# Ornament.net
KiCad netlist of a schematic drawn in Altium Designer
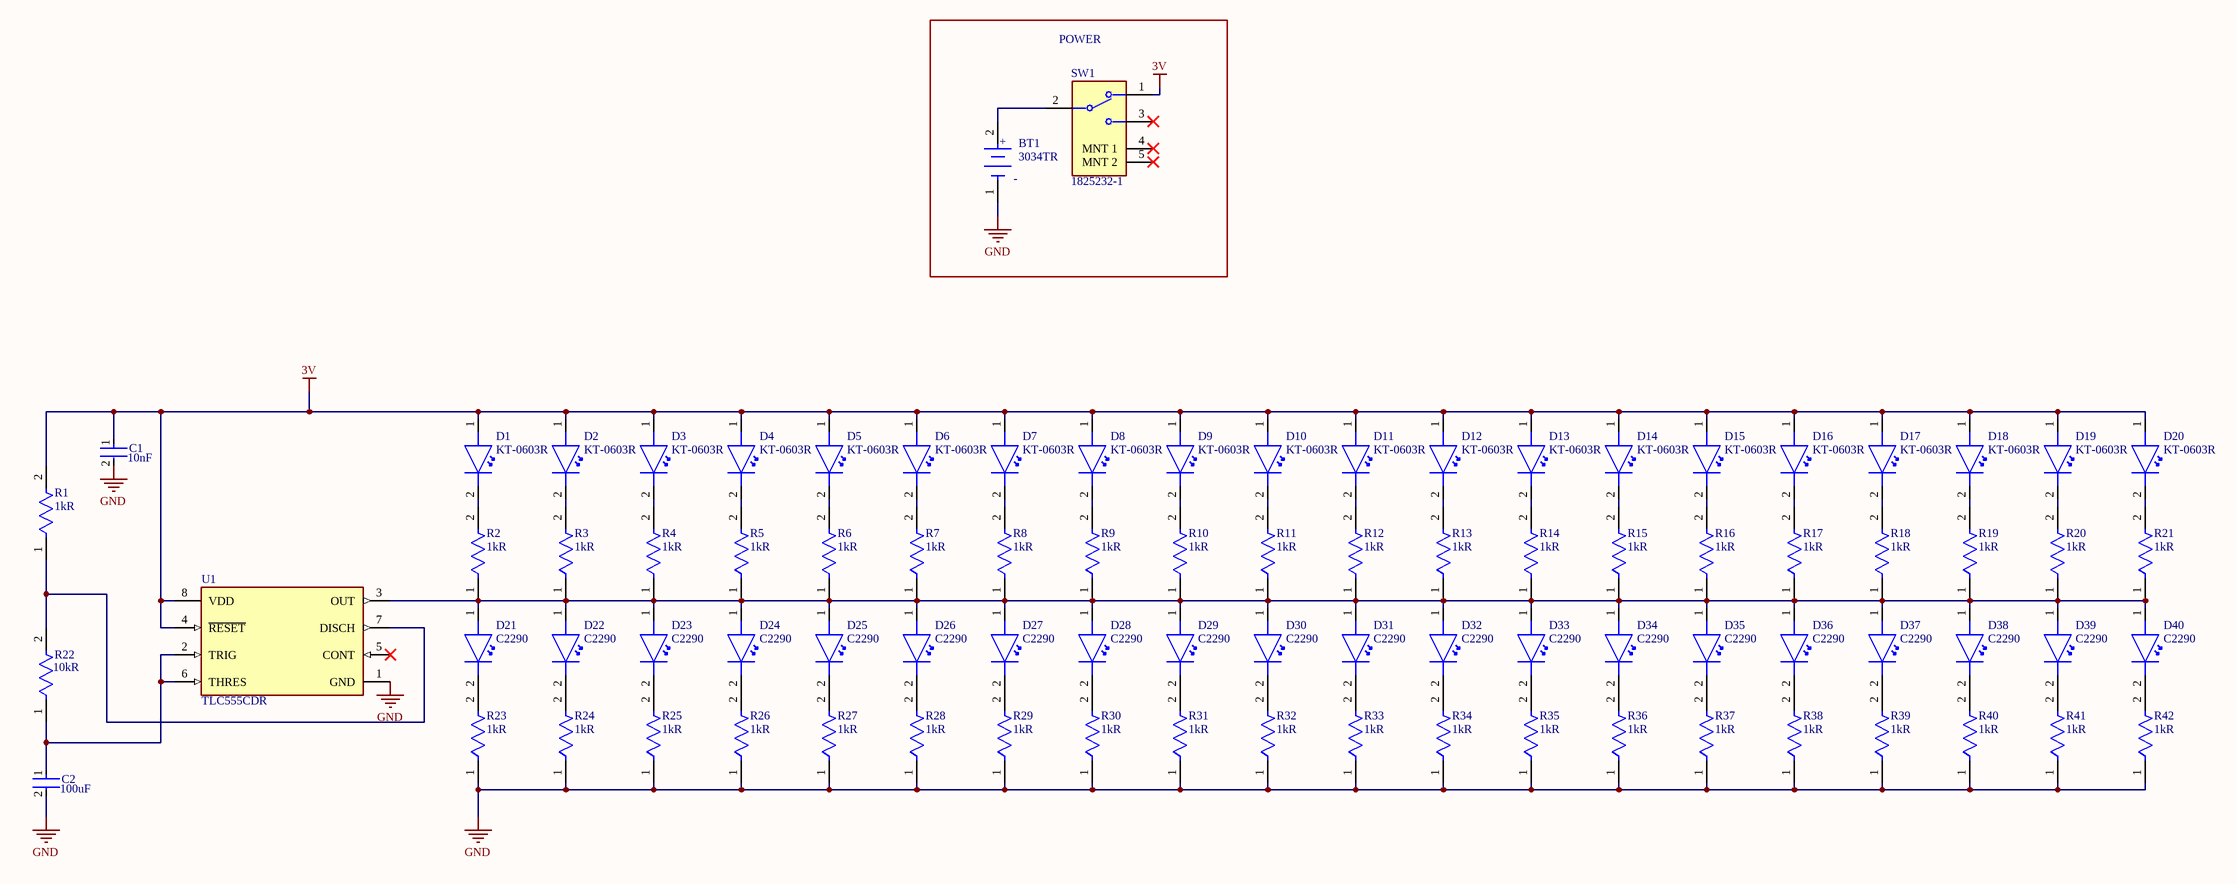
[diagram p0: Ornament.SchDoc]

(export (version "E")
  (design (tool "Eeschema 10.0.6"))
  (components
    (comp (ref "BT1")
      (value "3034TR")
      (footprint "FP-3034TR-MFG")
      (description "BATTERY RETAINER COIN 20MM SMD")
      (libsource (lib "Altium Content Vault") (part "a5284bd3cf3b31494a5f032c79b9da8"))
    )
    (comp (ref "C1")
      (value "CL05B103KB5NNNC")
      (footprint "FP-CL165-IPC_C")
      (description "Cap Ceramic 10nF 50V X7R ±10% SMD 0402 +125°C Paper T/R")
      (fields
        (field (name "VOLTAGE") "50V")
        (field (name "TOLERANCE") "10%")
        (field (name "CAPACITANCE") "10nF")
      )
      (libsource (lib "Altium Content Vault") (part "b4654b650e69147ec39a6b967a45e02"))
    )
    (comp (ref "C2")
      (value "JMK316BJ107ML-T")
      (footprint "FP-MK316L-MFG")
      (description "CAP CER 100UF 6.3V X5R 1206")
      (fields (field (name "CAPACITANCE") "100uF") (field (name "TOLERANCE") "2%"))
      (libsource (lib "Altium Content Vault") (part "b4654b650e69147ec39a6b967a45e02"))
    )
    (comp (ref "D1")
      (value "KT-0603R")
      (footprint "LED_0603")
      (description "Red 615~630nm 1.9~2.2V 0603 Light Emitting Diodes (LED) RoHS")
      (libsource (lib "Symbols") (part "KT-0603R"))
    )
    (comp (ref "D2")
      (value "KT-0603R")
      (footprint "LED_0603")
      (description "Red 615~630nm 1.9~2.2V 0603 Light Emitting Diodes (LED) RoHS")
      (libsource (lib "Symbols") (part "KT-0603R"))
    )
    (comp (ref "D3")
      (value "KT-0603R")
      (footprint "LED_0603")
      (description "Red 615~630nm 1.9~2.2V 0603 Light Emitting Diodes (LED) RoHS")
      (libsource (lib "Symbols") (part "KT-0603R"))
    )
    (comp (ref "D4")
      (value "KT-0603R")
      (footprint "LED_0603")
      (description "Red 615~630nm 1.9~2.2V 0603 Light Emitting Diodes (LED) RoHS")
      (libsource (lib "Symbols") (part "KT-0603R"))
    )
    (comp (ref "D5")
      (value "KT-0603R")
      (footprint "LED_0603")
      (description "Red 615~630nm 1.9~2.2V 0603 Light Emitting Diodes (LED) RoHS")
      (libsource (lib "Symbols") (part "KT-0603R"))
    )
    (comp (ref "D6")
      (value "KT-0603R")
      (footprint "LED_0603")
      (description "Red 615~630nm 1.9~2.2V 0603 Light Emitting Diodes (LED) RoHS")
      (libsource (lib "Symbols") (part "KT-0603R"))
    )
    (comp (ref "D7")
      (value "KT-0603R")
      (footprint "LED_0603")
      (description "Red 615~630nm 1.9~2.2V 0603 Light Emitting Diodes (LED) RoHS")
      (libsource (lib "Symbols") (part "KT-0603R"))
    )
    (comp (ref "D8")
      (value "KT-0603R")
      (footprint "LED_0603")
      (description "Red 615~630nm 1.9~2.2V 0603 Light Emitting Diodes (LED) RoHS")
      (libsource (lib "Symbols") (part "KT-0603R"))
    )
    (comp (ref "D9")
      (value "KT-0603R")
      (footprint "LED_0603")
      (description "Red 615~630nm 1.9~2.2V 0603 Light Emitting Diodes (LED) RoHS")
      (libsource (lib "Symbols") (part "KT-0603R"))
    )
    (comp (ref "D10")
      (value "KT-0603R")
      (footprint "LED_0603")
      (description "Red 615~630nm 1.9~2.2V 0603 Light Emitting Diodes (LED) RoHS")
      (libsource (lib "Symbols") (part "KT-0603R"))
    )
    (comp (ref "D11")
      (value "KT-0603R")
      (footprint "LED_0603")
      (description "Red 615~630nm 1.9~2.2V 0603 Light Emitting Diodes (LED) RoHS")
      (libsource (lib "Symbols") (part "KT-0603R"))
    )
    (comp (ref "D12")
      (value "KT-0603R")
      (footprint "LED_0603")
      (description "Red 615~630nm 1.9~2.2V 0603 Light Emitting Diodes (LED) RoHS")
      (libsource (lib "Symbols") (part "KT-0603R"))
    )
    (comp (ref "D13")
      (value "KT-0603R")
      (footprint "LED_0603")
      (description "Red 615~630nm 1.9~2.2V 0603 Light Emitting Diodes (LED) RoHS")
      (libsource (lib "Symbols") (part "KT-0603R"))
    )
    (comp (ref "D14")
      (value "KT-0603R")
      (footprint "LED_0603")
      (description "Red 615~630nm 1.9~2.2V 0603 Light Emitting Diodes (LED) RoHS")
      (libsource (lib "Symbols") (part "KT-0603R"))
    )
    (comp (ref "D15")
      (value "KT-0603R")
      (footprint "LED_0603")
      (description "Red 615~630nm 1.9~2.2V 0603 Light Emitting Diodes (LED) RoHS")
      (libsource (lib "Symbols") (part "KT-0603R"))
    )
    (comp (ref "D16")
      (value "KT-0603R")
      (footprint "LED_0603")
      (description "Red 615~630nm 1.9~2.2V 0603 Light Emitting Diodes (LED) RoHS")
      (libsource (lib "Symbols") (part "KT-0603R"))
    )
    (comp (ref "D17")
      (value "KT-0603R")
      (footprint "LED_0603")
      (description "Red 615~630nm 1.9~2.2V 0603 Light Emitting Diodes (LED) RoHS")
      (libsource (lib "Symbols") (part "KT-0603R"))
    )
    (comp (ref "D18")
      (value "KT-0603R")
      (footprint "LED_0603")
      (description "Red 615~630nm 1.9~2.2V 0603 Light Emitting Diodes (LED) RoHS")
      (libsource (lib "Symbols") (part "KT-0603R"))
    )
    (comp (ref "D19")
      (value "KT-0603R")
      (footprint "LED_0603")
      (description "Red 615~630nm 1.9~2.2V 0603 Light Emitting Diodes (LED) RoHS")
      (libsource (lib "Symbols") (part "KT-0603R"))
    )
    (comp (ref "D20")
      (value "KT-0603R")
      (footprint "LED_0603")
      (description "Red 615~630nm 1.9~2.2V 0603 Light Emitting Diodes (LED) RoHS")
      (libsource (lib "Symbols") (part "KT-0603R"))
    )
    (comp (ref "D21")
      (value "C2290")
      (footprint "LED_0603")
      (description "White 0603 Light Emitting Diodes (LED) RoHS")
      (libsource (lib "Symbols") (part "C2290"))
    )
    (comp (ref "D22")
      (value "C2290")
      (footprint "LED_0603")
      (description "White 0603 Light Emitting Diodes (LED) RoHS")
      (libsource (lib "Symbols") (part "C2290"))
    )
    (comp (ref "D23")
      (value "C2290")
      (footprint "LED_0603")
      (description "White 0603 Light Emitting Diodes (LED) RoHS")
      (libsource (lib "Symbols") (part "C2290"))
    )
    (comp (ref "D24")
      (value "C2290")
      (footprint "LED_0603")
      (description "White 0603 Light Emitting Diodes (LED) RoHS")
      (libsource (lib "Symbols") (part "C2290"))
    )
    (comp (ref "D25")
      (value "C2290")
      (footprint "LED_0603")
      (description "White 0603 Light Emitting Diodes (LED) RoHS")
      (libsource (lib "Symbols") (part "C2290"))
    )
    (comp (ref "D26")
      (value "C2290")
      (footprint "LED_0603")
      (description "White 0603 Light Emitting Diodes (LED) RoHS")
      (libsource (lib "Symbols") (part "C2290"))
    )
    (comp (ref "D27")
      (value "C2290")
      (footprint "LED_0603")
      (description "White 0603 Light Emitting Diodes (LED) RoHS")
      (libsource (lib "Symbols") (part "C2290"))
    )
    (comp (ref "D28")
      (value "C2290")
      (footprint "LED_0603")
      (description "White 0603 Light Emitting Diodes (LED) RoHS")
      (libsource (lib "Symbols") (part "C2290"))
    )
    (comp (ref "D29")
      (value "C2290")
      (footprint "LED_0603")
      (description "White 0603 Light Emitting Diodes (LED) RoHS")
      (libsource (lib "Symbols") (part "C2290"))
    )
    (comp (ref "D30")
      (value "C2290")
      (footprint "LED_0603")
      (description "White 0603 Light Emitting Diodes (LED) RoHS")
      (libsource (lib "Symbols") (part "C2290"))
    )
    (comp (ref "D31")
      (value "C2290")
      (footprint "LED_0603")
      (description "White 0603 Light Emitting Diodes (LED) RoHS")
      (libsource (lib "Symbols") (part "C2290"))
    )
    (comp (ref "D32")
      (value "C2290")
      (footprint "LED_0603")
      (description "White 0603 Light Emitting Diodes (LED) RoHS")
      (libsource (lib "Symbols") (part "C2290"))
    )
    (comp (ref "D33")
      (value "C2290")
      (footprint "LED_0603")
      (description "White 0603 Light Emitting Diodes (LED) RoHS")
      (libsource (lib "Symbols") (part "C2290"))
    )
    (comp (ref "D34")
      (value "C2290")
      (footprint "LED_0603")
      (description "White 0603 Light Emitting Diodes (LED) RoHS")
      (libsource (lib "Symbols") (part "C2290"))
    )
    (comp (ref "D35")
      (value "C2290")
      (footprint "LED_0603")
      (description "White 0603 Light Emitting Diodes (LED) RoHS")
      (libsource (lib "Symbols") (part "C2290"))
    )
    (comp (ref "D36")
      (value "C2290")
      (footprint "LED_0603")
      (description "White 0603 Light Emitting Diodes (LED) RoHS")
      (libsource (lib "Symbols") (part "C2290"))
    )
    (comp (ref "D37")
      (value "C2290")
      (footprint "LED_0603")
      (description "White 0603 Light Emitting Diodes (LED) RoHS")
      (libsource (lib "Symbols") (part "C2290"))
    )
    (comp (ref "D38")
      (value "C2290")
      (footprint "LED_0603")
      (description "White 0603 Light Emitting Diodes (LED) RoHS")
      (libsource (lib "Symbols") (part "C2290"))
    )
    (comp (ref "D39")
      (value "C2290")
      (footprint "LED_0603")
      (description "White 0603 Light Emitting Diodes (LED) RoHS")
      (libsource (lib "Symbols") (part "C2290"))
    )
    (comp (ref "D40")
      (value "C2290")
      (footprint "LED_0603")
      (description "White 0603 Light Emitting Diodes (LED) RoHS")
      (libsource (lib "Symbols") (part "C2290"))
    )
    (comp (ref "R1")
      (value "AC0402FR-071KL")
      (footprint "FP-AC0402-IPC_C")
      (description "RES 1kΩ ±1% 0.063W 0402")
      (fields (field (name "TOLERANCE") "1%") (field (name "RESISTANCE") "1kR"))
      (libsource (lib "Altium Content Vault") (part "1029c3af85768c4190bb7ad29bc67b5"))
    )
    (comp (ref "R2")
      (value "AC0402FR-071KL")
      (footprint "FP-AC0402-IPC_C")
      (description "RES 1kΩ ±1% 0.063W 0402")
      (fields (field (name "TOLERANCE") "1%") (field (name "RESISTANCE") "1kR"))
      (libsource (lib "Altium Content Vault") (part "1029c3af85768c4190bb7ad29bc67b5"))
    )
    (comp (ref "R3")
      (value "AC0402FR-071KL")
      (footprint "FP-AC0402-IPC_C")
      (description "RES 1kΩ ±1% 0.063W 0402")
      (fields (field (name "TOLERANCE") "1%") (field (name "RESISTANCE") "1kR"))
      (libsource (lib "Altium Content Vault") (part "1029c3af85768c4190bb7ad29bc67b5"))
    )
    (comp (ref "R4")
      (value "AC0402FR-071KL")
      (footprint "FP-AC0402-IPC_C")
      (description "RES 1kΩ ±1% 0.063W 0402")
      (fields (field (name "TOLERANCE") "1%") (field (name "RESISTANCE") "1kR"))
      (libsource (lib "Altium Content Vault") (part "1029c3af85768c4190bb7ad29bc67b5"))
    )
    (comp (ref "R5")
      (value "AC0402FR-071KL")
      (footprint "FP-AC0402-IPC_C")
      (description "RES 1kΩ ±1% 0.063W 0402")
      (fields (field (name "TOLERANCE") "1%") (field (name "RESISTANCE") "1kR"))
      (libsource (lib "Altium Content Vault") (part "1029c3af85768c4190bb7ad29bc67b5"))
    )
    (comp (ref "R6")
      (value "AC0402FR-071KL")
      (footprint "FP-AC0402-IPC_C")
      (description "RES 1kΩ ±1% 0.063W 0402")
      (fields (field (name "TOLERANCE") "1%") (field (name "RESISTANCE") "1kR"))
      (libsource (lib "Altium Content Vault") (part "1029c3af85768c4190bb7ad29bc67b5"))
    )
    (comp (ref "R7")
      (value "AC0402FR-071KL")
      (footprint "FP-AC0402-IPC_C")
      (description "RES 1kΩ ±1% 0.063W 0402")
      (fields (field (name "TOLERANCE") "1%") (field (name "RESISTANCE") "1kR"))
      (libsource (lib "Altium Content Vault") (part "1029c3af85768c4190bb7ad29bc67b5"))
    )
    (comp (ref "R8")
      (value "AC0402FR-071KL")
      (footprint "FP-AC0402-IPC_C")
      (description "RES 1kΩ ±1% 0.063W 0402")
      (fields (field (name "TOLERANCE") "1%") (field (name "RESISTANCE") "1kR"))
      (libsource (lib "Altium Content Vault") (part "1029c3af85768c4190bb7ad29bc67b5"))
    )
    (comp (ref "R9")
      (value "AC0402FR-071KL")
      (footprint "FP-AC0402-IPC_C")
      (description "RES 1kΩ ±1% 0.063W 0402")
      (fields (field (name "TOLERANCE") "1%") (field (name "RESISTANCE") "1kR"))
      (libsource (lib "Altium Content Vault") (part "1029c3af85768c4190bb7ad29bc67b5"))
    )
    (comp (ref "R10")
      (value "AC0402FR-071KL")
      (footprint "FP-AC0402-IPC_C")
      (description "RES 1kΩ ±1% 0.063W 0402")
      (fields (field (name "TOLERANCE") "1%") (field (name "RESISTANCE") "1kR"))
      (libsource (lib "Altium Content Vault") (part "1029c3af85768c4190bb7ad29bc67b5"))
    )
    (comp (ref "R11")
      (value "AC0402FR-071KL")
      (footprint "FP-AC0402-IPC_C")
      (description "RES 1kΩ ±1% 0.063W 0402")
      (fields (field (name "TOLERANCE") "1%") (field (name "RESISTANCE") "1kR"))
      (libsource (lib "Altium Content Vault") (part "1029c3af85768c4190bb7ad29bc67b5"))
    )
    (comp (ref "R12")
      (value "AC0402FR-071KL")
      (footprint "FP-AC0402-IPC_C")
      (description "RES 1kΩ ±1% 0.063W 0402")
      (fields (field (name "TOLERANCE") "1%") (field (name "RESISTANCE") "1kR"))
      (libsource (lib "Altium Content Vault") (part "1029c3af85768c4190bb7ad29bc67b5"))
    )
    (comp (ref "R13")
      (value "AC0402FR-071KL")
      (footprint "FP-AC0402-IPC_C")
      (description "RES 1kΩ ±1% 0.063W 0402")
      (fields (field (name "TOLERANCE") "1%") (field (name "RESISTANCE") "1kR"))
      (libsource (lib "Altium Content Vault") (part "1029c3af85768c4190bb7ad29bc67b5"))
    )
    (comp (ref "R14")
      (value "AC0402FR-071KL")
      (footprint "FP-AC0402-IPC_C")
      (description "RES 1kΩ ±1% 0.063W 0402")
      (fields (field (name "TOLERANCE") "1%") (field (name "RESISTANCE") "1kR"))
      (libsource (lib "Altium Content Vault") (part "1029c3af85768c4190bb7ad29bc67b5"))
    )
    (comp (ref "R15")
      (value "AC0402FR-071KL")
      (footprint "FP-AC0402-IPC_C")
      (description "RES 1kΩ ±1% 0.063W 0402")
      (fields (field (name "TOLERANCE") "1%") (field (name "RESISTANCE") "1kR"))
      (libsource (lib "Altium Content Vault") (part "1029c3af85768c4190bb7ad29bc67b5"))
    )
    (comp (ref "R16")
      (value "AC0402FR-071KL")
      (footprint "FP-AC0402-IPC_C")
      (description "RES 1kΩ ±1% 0.063W 0402")
      (fields (field (name "TOLERANCE") "1%") (field (name "RESISTANCE") "1kR"))
      (libsource (lib "Altium Content Vault") (part "1029c3af85768c4190bb7ad29bc67b5"))
    )
    (comp (ref "R17")
      (value "AC0402FR-071KL")
      (footprint "FP-AC0402-IPC_C")
      (description "RES 1kΩ ±1% 0.063W 0402")
      (fields (field (name "TOLERANCE") "1%") (field (name "RESISTANCE") "1kR"))
      (libsource (lib "Altium Content Vault") (part "1029c3af85768c4190bb7ad29bc67b5"))
    )
    (comp (ref "R18")
      (value "AC0402FR-071KL")
      (footprint "FP-AC0402-IPC_C")
      (description "RES 1kΩ ±1% 0.063W 0402")
      (fields (field (name "TOLERANCE") "1%") (field (name "RESISTANCE") "1kR"))
      (libsource (lib "Altium Content Vault") (part "1029c3af85768c4190bb7ad29bc67b5"))
    )
    (comp (ref "R19")
      (value "AC0402FR-071KL")
      (footprint "FP-AC0402-IPC_C")
      (description "RES 1kΩ ±1% 0.063W 0402")
      (fields (field (name "TOLERANCE") "1%") (field (name "RESISTANCE") "1kR"))
      (libsource (lib "Altium Content Vault") (part "1029c3af85768c4190bb7ad29bc67b5"))
    )
    (comp (ref "R20")
      (value "AC0402FR-071KL")
      (footprint "FP-AC0402-IPC_C")
      (description "RES 1kΩ ±1% 0.063W 0402")
      (fields (field (name "TOLERANCE") "1%") (field (name "RESISTANCE") "1kR"))
      (libsource (lib "Altium Content Vault") (part "1029c3af85768c4190bb7ad29bc67b5"))
    )
    (comp (ref "R21")
      (value "AC0402FR-071KL")
      (footprint "FP-AC0402-IPC_C")
      (description "RES 1kΩ ±1% 0.063W 0402")
      (fields (field (name "TOLERANCE") "1%") (field (name "RESISTANCE") "1kR"))
      (libsource (lib "Altium Content Vault") (part "1029c3af85768c4190bb7ad29bc67b5"))
    )
    (comp (ref "R22")
      (value "AC0402FR-0710KL")
      (footprint "FP-AC0402-MFG")
      (description "RES 10kΩ ±1% 0.063W 0402")
      (fields (field (name "TOLERANCE") "1%") (field (name "RESISTANCE") "10kR"))
      (libsource (lib "Altium Content Vault") (part "1029c3af85768c4190bb7ad29bc67b5"))
    )
    (comp (ref "R23")
      (value "AC0402FR-071KL")
      (footprint "FP-AC0402-IPC_C")
      (description "RES 1kΩ ±1% 0.063W 0402")
      (fields (field (name "TOLERANCE") "1%") (field (name "RESISTANCE") "1kR"))
      (libsource (lib "Altium Content Vault") (part "1029c3af85768c4190bb7ad29bc67b5"))
    )
    (comp (ref "R24")
      (value "AC0402FR-071KL")
      (footprint "FP-AC0402-IPC_C")
      (description "RES 1kΩ ±1% 0.063W 0402")
      (fields (field (name "TOLERANCE") "1%") (field (name "RESISTANCE") "1kR"))
      (libsource (lib "Altium Content Vault") (part "1029c3af85768c4190bb7ad29bc67b5"))
    )
    (comp (ref "R25")
      (value "AC0402FR-071KL")
      (footprint "FP-AC0402-IPC_C")
      (description "RES 1kΩ ±1% 0.063W 0402")
      (fields (field (name "TOLERANCE") "1%") (field (name "RESISTANCE") "1kR"))
      (libsource (lib "Altium Content Vault") (part "1029c3af85768c4190bb7ad29bc67b5"))
    )
    (comp (ref "R26")
      (value "AC0402FR-071KL")
      (footprint "FP-AC0402-IPC_C")
      (description "RES 1kΩ ±1% 0.063W 0402")
      (fields (field (name "TOLERANCE") "1%") (field (name "RESISTANCE") "1kR"))
      (libsource (lib "Altium Content Vault") (part "1029c3af85768c4190bb7ad29bc67b5"))
    )
    (comp (ref "R27")
      (value "AC0402FR-071KL")
      (footprint "FP-AC0402-IPC_C")
      (description "RES 1kΩ ±1% 0.063W 0402")
      (fields (field (name "TOLERANCE") "1%") (field (name "RESISTANCE") "1kR"))
      (libsource (lib "Altium Content Vault") (part "1029c3af85768c4190bb7ad29bc67b5"))
    )
    (comp (ref "R28")
      (value "AC0402FR-071KL")
      (footprint "FP-AC0402-IPC_C")
      (description "RES 1kΩ ±1% 0.063W 0402")
      (fields (field (name "TOLERANCE") "1%") (field (name "RESISTANCE") "1kR"))
      (libsource (lib "Altium Content Vault") (part "1029c3af85768c4190bb7ad29bc67b5"))
    )
    (comp (ref "R29")
      (value "AC0402FR-071KL")
      (footprint "FP-AC0402-IPC_C")
      (description "RES 1kΩ ±1% 0.063W 0402")
      (fields (field (name "TOLERANCE") "1%") (field (name "RESISTANCE") "1kR"))
      (libsource (lib "Altium Content Vault") (part "1029c3af85768c4190bb7ad29bc67b5"))
    )
    (comp (ref "R30")
      (value "AC0402FR-071KL")
      (footprint "FP-AC0402-IPC_C")
      (description "RES 1kΩ ±1% 0.063W 0402")
      (fields (field (name "TOLERANCE") "1%") (field (name "RESISTANCE") "1kR"))
      (libsource (lib "Altium Content Vault") (part "1029c3af85768c4190bb7ad29bc67b5"))
    )
    (comp (ref "R31")
      (value "AC0402FR-071KL")
      (footprint "FP-AC0402-IPC_C")
      (description "RES 1kΩ ±1% 0.063W 0402")
      (fields (field (name "TOLERANCE") "1%") (field (name "RESISTANCE") "1kR"))
      (libsource (lib "Altium Content Vault") (part "1029c3af85768c4190bb7ad29bc67b5"))
    )
    (comp (ref "R32")
      (value "AC0402FR-071KL")
      (footprint "FP-AC0402-IPC_C")
      (description "RES 1kΩ ±1% 0.063W 0402")
      (fields (field (name "TOLERANCE") "1%") (field (name "RESISTANCE") "1kR"))
      (libsource (lib "Altium Content Vault") (part "1029c3af85768c4190bb7ad29bc67b5"))
    )
    (comp (ref "R33")
      (value "AC0402FR-071KL")
      (footprint "FP-AC0402-IPC_C")
      (description "RES 1kΩ ±1% 0.063W 0402")
      (fields (field (name "TOLERANCE") "1%") (field (name "RESISTANCE") "1kR"))
      (libsource (lib "Altium Content Vault") (part "1029c3af85768c4190bb7ad29bc67b5"))
    )
    (comp (ref "R34")
      (value "AC0402FR-071KL")
      (footprint "FP-AC0402-IPC_C")
      (description "RES 1kΩ ±1% 0.063W 0402")
      (fields (field (name "TOLERANCE") "1%") (field (name "RESISTANCE") "1kR"))
      (libsource (lib "Altium Content Vault") (part "1029c3af85768c4190bb7ad29bc67b5"))
    )
    (comp (ref "R35")
      (value "AC0402FR-071KL")
      (footprint "FP-AC0402-IPC_C")
      (description "RES 1kΩ ±1% 0.063W 0402")
      (fields (field (name "TOLERANCE") "1%") (field (name "RESISTANCE") "1kR"))
      (libsource (lib "Altium Content Vault") (part "1029c3af85768c4190bb7ad29bc67b5"))
    )
    (comp (ref "R36")
      (value "AC0402FR-071KL")
      (footprint "FP-AC0402-IPC_C")
      (description "RES 1kΩ ±1% 0.063W 0402")
      (fields (field (name "TOLERANCE") "1%") (field (name "RESISTANCE") "1kR"))
      (libsource (lib "Altium Content Vault") (part "1029c3af85768c4190bb7ad29bc67b5"))
    )
    (comp (ref "R37")
      (value "AC0402FR-071KL")
      (footprint "FP-AC0402-IPC_C")
      (description "RES 1kΩ ±1% 0.063W 0402")
      (fields (field (name "TOLERANCE") "1%") (field (name "RESISTANCE") "1kR"))
      (libsource (lib "Altium Content Vault") (part "1029c3af85768c4190bb7ad29bc67b5"))
    )
    (comp (ref "R38")
      (value "AC0402FR-071KL")
      (footprint "FP-AC0402-IPC_C")
      (description "RES 1kΩ ±1% 0.063W 0402")
      (fields (field (name "TOLERANCE") "1%") (field (name "RESISTANCE") "1kR"))
      (libsource (lib "Altium Content Vault") (part "1029c3af85768c4190bb7ad29bc67b5"))
    )
    (comp (ref "R39")
      (value "AC0402FR-071KL")
      (footprint "FP-AC0402-IPC_C")
      (description "RES 1kΩ ±1% 0.063W 0402")
      (fields (field (name "TOLERANCE") "1%") (field (name "RESISTANCE") "1kR"))
      (libsource (lib "Altium Content Vault") (part "1029c3af85768c4190bb7ad29bc67b5"))
    )
    (comp (ref "R40")
      (value "AC0402FR-071KL")
      (footprint "FP-AC0402-IPC_C")
      (description "RES 1kΩ ±1% 0.063W 0402")
      (fields (field (name "TOLERANCE") "1%") (field (name "RESISTANCE") "1kR"))
      (libsource (lib "Altium Content Vault") (part "1029c3af85768c4190bb7ad29bc67b5"))
    )
    (comp (ref "R41")
      (value "AC0402FR-071KL")
      (footprint "FP-AC0402-IPC_C")
      (description "RES 1kΩ ±1% 0.063W 0402")
      (fields (field (name "TOLERANCE") "1%") (field (name "RESISTANCE") "1kR"))
      (libsource (lib "Altium Content Vault") (part "1029c3af85768c4190bb7ad29bc67b5"))
    )
    (comp (ref "R42")
      (value "AC0402FR-071KL")
      (footprint "FP-AC0402-IPC_C")
      (description "RES 1kΩ ±1% 0.063W 0402")
      (fields (field (name "TOLERANCE") "1%") (field (name "RESISTANCE") "1kR"))
      (libsource (lib "Altium Content Vault") (part "1029c3af85768c4190bb7ad29bc67b5"))
    )
    (comp (ref "SW1")
      (value "1825232-1")
      (footprint "FP-1825232-1-MFG")
      (description "Switch Slide ON None ON SPDT Side Slide 0.2A 30VDC 10000Cycle PC Pins Bracket Mount/Through Hole")
      (fields (field (name "OCTOPART") "https://octopart.com/1825232-1-te+connectivity-45209882"))
      (libsource (lib "Altium Content Vault") (part "b81b21e7de6c425a317152e587b8097"))
    )
    (comp (ref "U1")
      (value "TLC555CDR")
      (footprint "FP-D0008A-IPC_B")
      (description "IC OSC SGL TIMER 2.1MHZ 8-SOIC")
      (libsource (lib "Altium Content Vault") (part "fd1638d23bf5e420a54176ee4f8e783"))
    )
  )
  (nets
    (net (code "1") (name "3V") (class "Default")
      (node (ref "C1") (pin "1") (pinfunction "1_1") (pintype "passive"))
      (node (ref "D1") (pin "1") (pintype "passive"))
      (node (ref "D10") (pin "1") (pintype "passive"))
      (node (ref "D11") (pin "1") (pintype "passive"))
      (node (ref "D12") (pin "1") (pintype "passive"))
      (node (ref "D13") (pin "1") (pintype "passive"))
      (node (ref "D14") (pin "1") (pintype "passive"))
      (node (ref "D15") (pin "1") (pintype "passive"))
      (node (ref "D16") (pin "1") (pintype "passive"))
      (node (ref "D17") (pin "1") (pintype "passive"))
      (node (ref "D18") (pin "1") (pintype "passive"))
      (node (ref "D19") (pin "1") (pintype "passive"))
      (node (ref "D2") (pin "1") (pintype "passive"))
      (node (ref "D20") (pin "1") (pintype "passive"))
      (node (ref "D3") (pin "1") (pintype "passive"))
      (node (ref "D4") (pin "1") (pintype "passive"))
      (node (ref "D5") (pin "1") (pintype "passive"))
      (node (ref "D6") (pin "1") (pintype "passive"))
      (node (ref "D7") (pin "1") (pintype "passive"))
      (node (ref "D8") (pin "1") (pintype "passive"))
      (node (ref "D9") (pin "1") (pintype "passive"))
      (node (ref "R1") (pin "2") (pinfunction "2_2") (pintype "passive"))
      (node (ref "SW1") (pin "1") (pinfunction "1_1") (pintype "passive"))
      (node (ref "U1") (pin "4") (pinfunction "~{RESET}_4") (pintype "input"))
      (node (ref "U1") (pin "8") (pinfunction "VDD_8") (pintype "power_in"))
    )
    (net (code "2") (name "GND") (class "Default")
      (node (ref "BT1") (pin "1") (pinfunction "C_1") (pintype "passive"))
      (node (ref "C1") (pin "2") (pinfunction "2_2") (pintype "passive"))
      (node (ref "C2") (pin "2") (pinfunction "2_2") (pintype "passive"))
      (node (ref "R23") (pin "1") (pinfunction "1_1") (pintype "passive"))
      (node (ref "R24") (pin "1") (pinfunction "1_1") (pintype "passive"))
      (node (ref "R25") (pin "1") (pinfunction "1_1") (pintype "passive"))
      (node (ref "R26") (pin "1") (pinfunction "1_1") (pintype "passive"))
      (node (ref "R27") (pin "1") (pinfunction "1_1") (pintype "passive"))
      (node (ref "R28") (pin "1") (pinfunction "1_1") (pintype "passive"))
      (node (ref "R29") (pin "1") (pinfunction "1_1") (pintype "passive"))
      (node (ref "R30") (pin "1") (pinfunction "1_1") (pintype "passive"))
      (node (ref "R31") (pin "1") (pinfunction "1_1") (pintype "passive"))
      (node (ref "R32") (pin "1") (pinfunction "1_1") (pintype "passive"))
      (node (ref "R33") (pin "1") (pinfunction "1_1") (pintype "passive"))
      (node (ref "R34") (pin "1") (pinfunction "1_1") (pintype "passive"))
      (node (ref "R35") (pin "1") (pinfunction "1_1") (pintype "passive"))
      (node (ref "R36") (pin "1") (pinfunction "1_1") (pintype "passive"))
      (node (ref "R37") (pin "1") (pinfunction "1_1") (pintype "passive"))
      (node (ref "R38") (pin "1") (pinfunction "1_1") (pintype "passive"))
      (node (ref "R39") (pin "1") (pinfunction "1_1") (pintype "passive"))
      (node (ref "R40") (pin "1") (pinfunction "1_1") (pintype "passive"))
      (node (ref "R41") (pin "1") (pinfunction "1_1") (pintype "passive"))
      (node (ref "R42") (pin "1") (pinfunction "1_1") (pintype "passive"))
      (node (ref "U1") (pin "1") (pinfunction "GND_1") (pintype "power_in"))
    )
    (net (code "3") (name "Net-(BT1-A)") (class "Default")
      (node (ref "BT1") (pin "2") (pinfunction "A_2") (pintype "passive"))
      (node (ref "SW1") (pin "2") (pinfunction "2_2") (pintype "passive"))
    )
    (net (code "4") (name "Net-(D1-Pad2)") (class "Default")
      (node (ref "D1") (pin "2") (pinfunction "2_2") (pintype "passive"))
      (node (ref "R2") (pin "2") (pinfunction "2_2") (pintype "passive"))
    )
    (net (code "5") (name "Net-(D2-Pad2)") (class "Default")
      (node (ref "D2") (pin "2") (pinfunction "2_2") (pintype "passive"))
      (node (ref "R3") (pin "2") (pinfunction "2_2") (pintype "passive"))
    )
    (net (code "6") (name "Net-(D3-Pad2)") (class "Default")
      (node (ref "D3") (pin "2") (pinfunction "2_2") (pintype "passive"))
      (node (ref "R4") (pin "2") (pinfunction "2_2") (pintype "passive"))
    )
    (net (code "7") (name "Net-(D4-Pad2)") (class "Default")
      (node (ref "D4") (pin "2") (pinfunction "2_2") (pintype "passive"))
      (node (ref "R5") (pin "2") (pinfunction "2_2") (pintype "passive"))
    )
    (net (code "8") (name "Net-(D5-Pad2)") (class "Default")
      (node (ref "D5") (pin "2") (pinfunction "2_2") (pintype "passive"))
      (node (ref "R6") (pin "2") (pinfunction "2_2") (pintype "passive"))
    )
    (net (code "9") (name "Net-(D6-Pad2)") (class "Default")
      (node (ref "D6") (pin "2") (pinfunction "2_2") (pintype "passive"))
      (node (ref "R7") (pin "2") (pinfunction "2_2") (pintype "passive"))
    )
    (net (code "10") (name "Net-(D7-Pad2)") (class "Default")
      (node (ref "D7") (pin "2") (pinfunction "2_2") (pintype "passive"))
      (node (ref "R8") (pin "2") (pinfunction "2_2") (pintype "passive"))
    )
    (net (code "11") (name "Net-(D8-Pad2)") (class "Default")
      (node (ref "D8") (pin "2") (pinfunction "2_2") (pintype "passive"))
      (node (ref "R9") (pin "2") (pinfunction "2_2") (pintype "passive"))
    )
    (net (code "12") (name "Net-(D9-Pad2)") (class "Default")
      (node (ref "D9") (pin "2") (pinfunction "2_2") (pintype "passive"))
      (node (ref "R10") (pin "2") (pinfunction "2_2") (pintype "passive"))
    )
    (net (code "13") (name "Net-(D10-Pad2)") (class "Default")
      (node (ref "D10") (pin "2") (pinfunction "2_2") (pintype "passive"))
      (node (ref "R11") (pin "2") (pinfunction "2_2") (pintype "passive"))
    )
    (net (code "14") (name "Net-(D11-Pad2)") (class "Default")
      (node (ref "D11") (pin "2") (pinfunction "2_2") (pintype "passive"))
      (node (ref "R12") (pin "2") (pinfunction "2_2") (pintype "passive"))
    )
    (net (code "15") (name "Net-(D12-Pad2)") (class "Default")
      (node (ref "D12") (pin "2") (pinfunction "2_2") (pintype "passive"))
      (node (ref "R13") (pin "2") (pinfunction "2_2") (pintype "passive"))
    )
    (net (code "16") (name "Net-(D13-Pad2)") (class "Default")
      (node (ref "D13") (pin "2") (pinfunction "2_2") (pintype "passive"))
      (node (ref "R14") (pin "2") (pinfunction "2_2") (pintype "passive"))
    )
    (net (code "17") (name "Net-(D14-Pad2)") (class "Default")
      (node (ref "D14") (pin "2") (pinfunction "2_2") (pintype "passive"))
      (node (ref "R15") (pin "2") (pinfunction "2_2") (pintype "passive"))
    )
    (net (code "18") (name "Net-(D15-Pad2)") (class "Default")
      (node (ref "D15") (pin "2") (pinfunction "2_2") (pintype "passive"))
      (node (ref "R16") (pin "2") (pinfunction "2_2") (pintype "passive"))
    )
    (net (code "19") (name "Net-(D16-Pad2)") (class "Default")
      (node (ref "D16") (pin "2") (pinfunction "2_2") (pintype "passive"))
      (node (ref "R17") (pin "2") (pinfunction "2_2") (pintype "passive"))
    )
    (net (code "20") (name "Net-(D17-Pad2)") (class "Default")
      (node (ref "D17") (pin "2") (pinfunction "2_2") (pintype "passive"))
      (node (ref "R18") (pin "2") (pinfunction "2_2") (pintype "passive"))
    )
    (net (code "21") (name "Net-(D18-Pad2)") (class "Default")
      (node (ref "D18") (pin "2") (pinfunction "2_2") (pintype "passive"))
      (node (ref "R19") (pin "2") (pinfunction "2_2") (pintype "passive"))
    )
    (net (code "22") (name "Net-(D19-Pad2)") (class "Default")
      (node (ref "D19") (pin "2") (pinfunction "2_2") (pintype "passive"))
      (node (ref "R20") (pin "2") (pinfunction "2_2") (pintype "passive"))
    )
    (net (code "23") (name "Net-(D20-Pad2)") (class "Default")
      (node (ref "D20") (pin "2") (pinfunction "2_2") (pintype "passive"))
      (node (ref "R21") (pin "2") (pinfunction "2_2") (pintype "passive"))
    )
    (net (code "24") (name "Net-(D21-Pad2)") (class "Default")
      (node (ref "D21") (pin "2") (pinfunction "2_2") (pintype "passive"))
      (node (ref "R23") (pin "2") (pinfunction "2_2") (pintype "passive"))
    )
    (net (code "25") (name "Net-(D22-Pad2)") (class "Default")
      (node (ref "D22") (pin "2") (pinfunction "2_2") (pintype "passive"))
      (node (ref "R24") (pin "2") (pinfunction "2_2") (pintype "passive"))
    )
    (net (code "26") (name "Net-(D23-Pad2)") (class "Default")
      (node (ref "D23") (pin "2") (pinfunction "2_2") (pintype "passive"))
      (node (ref "R25") (pin "2") (pinfunction "2_2") (pintype "passive"))
    )
    (net (code "27") (name "Net-(D24-Pad2)") (class "Default")
      (node (ref "D24") (pin "2") (pinfunction "2_2") (pintype "passive"))
      (node (ref "R26") (pin "2") (pinfunction "2_2") (pintype "passive"))
    )
    (net (code "28") (name "Net-(D25-Pad2)") (class "Default")
      (node (ref "D25") (pin "2") (pinfunction "2_2") (pintype "passive"))
      (node (ref "R27") (pin "2") (pinfunction "2_2") (pintype "passive"))
    )
    (net (code "29") (name "Net-(D26-Pad2)") (class "Default")
      (node (ref "D26") (pin "2") (pinfunction "2_2") (pintype "passive"))
      (node (ref "R28") (pin "2") (pinfunction "2_2") (pintype "passive"))
    )
    (net (code "30") (name "Net-(D27-Pad2)") (class "Default")
      (node (ref "D27") (pin "2") (pinfunction "2_2") (pintype "passive"))
      (node (ref "R29") (pin "2") (pinfunction "2_2") (pintype "passive"))
    )
    (net (code "31") (name "Net-(D28-Pad2)") (class "Default")
      (node (ref "D28") (pin "2") (pinfunction "2_2") (pintype "passive"))
      (node (ref "R30") (pin "2") (pinfunction "2_2") (pintype "passive"))
    )
    (net (code "32") (name "Net-(D29-Pad2)") (class "Default")
      (node (ref "D29") (pin "2") (pinfunction "2_2") (pintype "passive"))
      (node (ref "R31") (pin "2") (pinfunction "2_2") (pintype "passive"))
    )
    (net (code "33") (name "Net-(D30-Pad2)") (class "Default")
      (node (ref "D30") (pin "2") (pinfunction "2_2") (pintype "passive"))
      (node (ref "R32") (pin "2") (pinfunction "2_2") (pintype "passive"))
    )
    (net (code "34") (name "Net-(D31-Pad2)") (class "Default")
      (node (ref "D31") (pin "2") (pinfunction "2_2") (pintype "passive"))
      (node (ref "R33") (pin "2") (pinfunction "2_2") (pintype "passive"))
    )
    (net (code "35") (name "Net-(D32-Pad2)") (class "Default")
      (node (ref "D32") (pin "2") (pinfunction "2_2") (pintype "passive"))
      (node (ref "R34") (pin "2") (pinfunction "2_2") (pintype "passive"))
    )
    (net (code "36") (name "Net-(D33-Pad2)") (class "Default")
      (node (ref "D33") (pin "2") (pinfunction "2_2") (pintype "passive"))
      (node (ref "R35") (pin "2") (pinfunction "2_2") (pintype "passive"))
    )
    (net (code "37") (name "Net-(D34-Pad2)") (class "Default")
      (node (ref "D34") (pin "2") (pinfunction "2_2") (pintype "passive"))
      (node (ref "R36") (pin "2") (pinfunction "2_2") (pintype "passive"))
    )
    (net (code "38") (name "Net-(D35-Pad2)") (class "Default")
      (node (ref "D35") (pin "2") (pinfunction "2_2") (pintype "passive"))
      (node (ref "R37") (pin "2") (pinfunction "2_2") (pintype "passive"))
    )
    (net (code "39") (name "Net-(D36-Pad2)") (class "Default")
      (node (ref "D36") (pin "2") (pinfunction "2_2") (pintype "passive"))
      (node (ref "R38") (pin "2") (pinfunction "2_2") (pintype "passive"))
    )
    (net (code "40") (name "Net-(D37-Pad2)") (class "Default")
      (node (ref "D37") (pin "2") (pinfunction "2_2") (pintype "passive"))
      (node (ref "R39") (pin "2") (pinfunction "2_2") (pintype "passive"))
    )
    (net (code "41") (name "Net-(D38-Pad2)") (class "Default")
      (node (ref "D38") (pin "2") (pinfunction "2_2") (pintype "passive"))
      (node (ref "R40") (pin "2") (pinfunction "2_2") (pintype "passive"))
    )
    (net (code "42") (name "Net-(D39-Pad2)") (class "Default")
      (node (ref "D39") (pin "2") (pinfunction "2_2") (pintype "passive"))
      (node (ref "R41") (pin "2") (pinfunction "2_2") (pintype "passive"))
    )
    (net (code "43") (name "Net-(D40-Pad2)") (class "Default")
      (node (ref "D40") (pin "2") (pinfunction "2_2") (pintype "passive"))
      (node (ref "R42") (pin "2") (pinfunction "2_2") (pintype "passive"))
    )
    (net (code "44") (name "Net-(U1-DISCH)") (class "Default")
      (node (ref "R1") (pin "1") (pinfunction "1_1") (pintype "passive"))
      (node (ref "R22") (pin "2") (pinfunction "2_2") (pintype "passive"))
      (node (ref "U1") (pin "7") (pinfunction "DISCH_7") (pintype "output"))
    )
    (net (code "45") (name "Net-(U1-OUT)") (class "Default")
      (node (ref "D21") (pin "1") (pintype "passive"))
      (node (ref "D22") (pin "1") (pintype "passive"))
      (node (ref "D23") (pin "1") (pintype "passive"))
      (node (ref "D24") (pin "1") (pintype "passive"))
      (node (ref "D25") (pin "1") (pintype "passive"))
      (node (ref "D26") (pin "1") (pintype "passive"))
      (node (ref "D27") (pin "1") (pintype "passive"))
      (node (ref "D28") (pin "1") (pintype "passive"))
      (node (ref "D29") (pin "1") (pintype "passive"))
      (node (ref "D30") (pin "1") (pintype "passive"))
      (node (ref "D31") (pin "1") (pintype "passive"))
      (node (ref "D32") (pin "1") (pintype "passive"))
      (node (ref "D33") (pin "1") (pintype "passive"))
      (node (ref "D34") (pin "1") (pintype "passive"))
      (node (ref "D35") (pin "1") (pintype "passive"))
      (node (ref "D36") (pin "1") (pintype "passive"))
      (node (ref "D37") (pin "1") (pintype "passive"))
      (node (ref "D38") (pin "1") (pintype "passive"))
      (node (ref "D39") (pin "1") (pintype "passive"))
      (node (ref "D40") (pin "1") (pintype "passive"))
      (node (ref "R10") (pin "1") (pinfunction "1_1") (pintype "passive"))
      (node (ref "R11") (pin "1") (pinfunction "1_1") (pintype "passive"))
      (node (ref "R12") (pin "1") (pinfunction "1_1") (pintype "passive"))
      (node (ref "R13") (pin "1") (pinfunction "1_1") (pintype "passive"))
      (node (ref "R14") (pin "1") (pinfunction "1_1") (pintype "passive"))
      (node (ref "R15") (pin "1") (pinfunction "1_1") (pintype "passive"))
      (node (ref "R16") (pin "1") (pinfunction "1_1") (pintype "passive"))
      (node (ref "R17") (pin "1") (pinfunction "1_1") (pintype "passive"))
      (node (ref "R18") (pin "1") (pinfunction "1_1") (pintype "passive"))
      (node (ref "R19") (pin "1") (pinfunction "1_1") (pintype "passive"))
      (node (ref "R2") (pin "1") (pinfunction "1_1") (pintype "passive"))
      (node (ref "R20") (pin "1") (pinfunction "1_1") (pintype "passive"))
      (node (ref "R21") (pin "1") (pinfunction "1_1") (pintype "passive"))
      (node (ref "R3") (pin "1") (pinfunction "1_1") (pintype "passive"))
      (node (ref "R4") (pin "1") (pinfunction "1_1") (pintype "passive"))
      (node (ref "R5") (pin "1") (pinfunction "1_1") (pintype "passive"))
      (node (ref "R6") (pin "1") (pinfunction "1_1") (pintype "passive"))
      (node (ref "R7") (pin "1") (pinfunction "1_1") (pintype "passive"))
      (node (ref "R8") (pin "1") (pinfunction "1_1") (pintype "passive"))
      (node (ref "R9") (pin "1") (pinfunction "1_1") (pintype "passive"))
      (node (ref "U1") (pin "3") (pinfunction "OUT_3") (pintype "output"))
    )
    (net (code "46") (name "Net-(U1-THRES)") (class "Default")
      (node (ref "C2") (pin "1") (pinfunction "1_1") (pintype "passive"))
      (node (ref "R22") (pin "1") (pinfunction "1_1") (pintype "passive"))
      (node (ref "U1") (pin "2") (pinfunction "TRIG_2") (pintype "input"))
      (node (ref "U1") (pin "6") (pinfunction "THRES_6") (pintype "input"))
    )
    (net (code "47") (name "unconnected-(SW1-MNT_1-Pad4)") (class "Default")
      (node (ref "SW1") (pin "4") (pinfunction "MNT_1_4") (pintype "passive+no_connect"))
    )
    (net (code "48") (name "unconnected-(SW1-MNT_2-Pad5)") (class "Default")
      (node (ref "SW1") (pin "5") (pinfunction "MNT_2_5") (pintype "passive+no_connect"))
    )
    (net (code "49") (name "unconnected-(SW1-Pad3)") (class "Default")
      (node (ref "SW1") (pin "3") (pinfunction "3_3") (pintype "passive+no_connect"))
    )
    (net (code "50") (name "unconnected-(U1-CONT-Pad5)") (class "Default")
      (node (ref "U1") (pin "5") (pinfunction "CONT_5") (pintype "input+no_connect"))
    )
  )
)
